# Rev_A.net
KiCad netlist of a schematic drawn in EAGLE
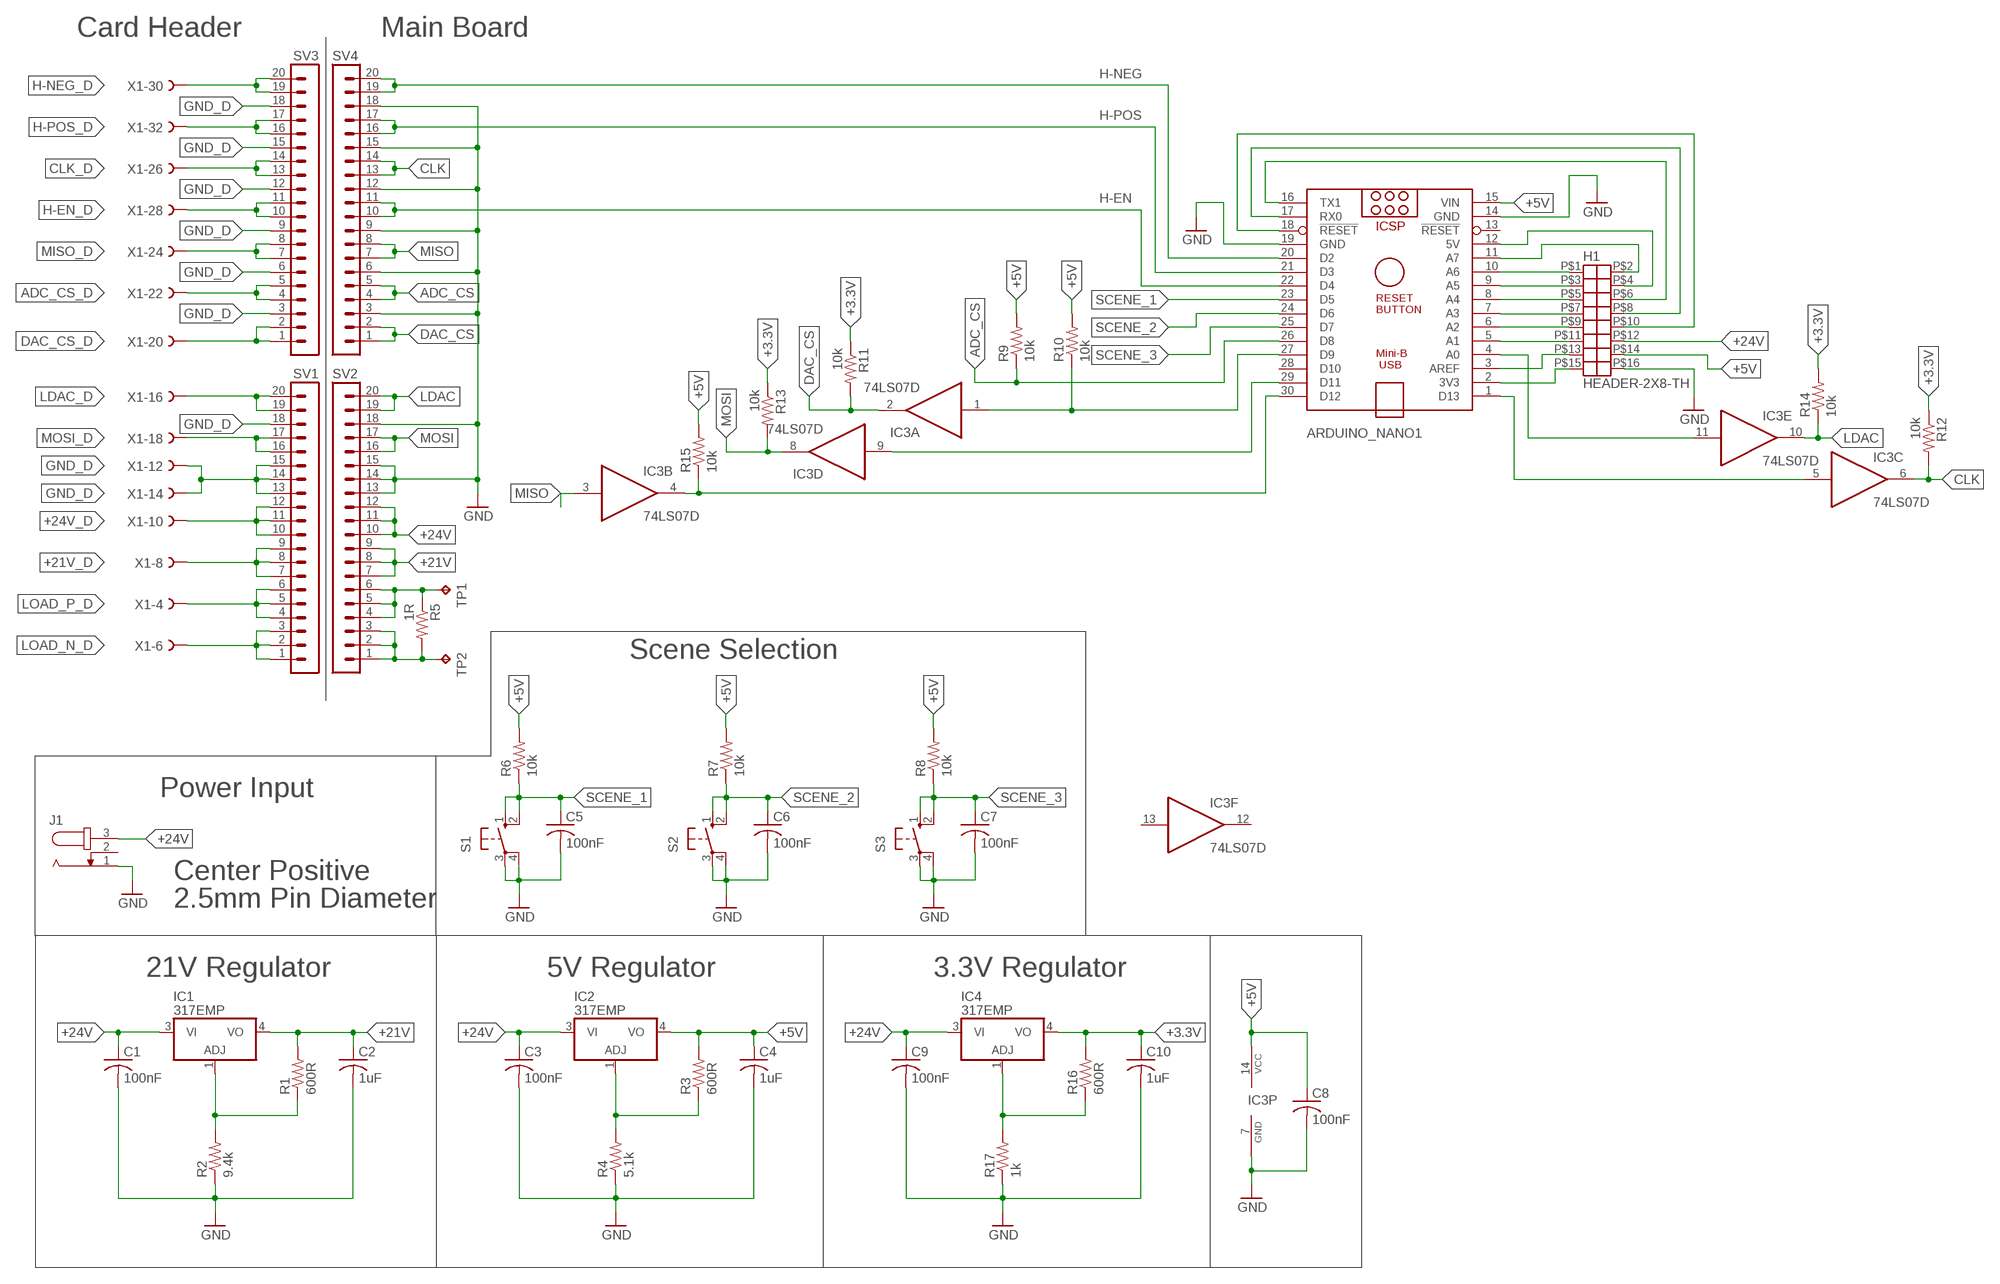
[diagram p0: schematic, sheet 1]

(export (version "E")
  (design (tool "Eeschema 10.0.6"))
  (components
    (comp (ref "ARDUINO_NANO1")
      (value "ARDUINO_NANO")
      (footprint "eagle-import:ARDUINO_NANO")
      (libsource (lib "eagle-import") (part "ARDUINO_NANO"))
    )
    (comp (ref "C1")
      (value "100nF")
      (footprint "eagle-import:C0603")
      (libsource (lib "eagle-import") (part "C-USC0603"))
    )
    (comp (ref "C2")
      (value "1uF")
      (footprint "eagle-import:C1206")
      (libsource (lib "eagle-import") (part "C-USC1206"))
    )
    (comp (ref "C3")
      (value "100nF")
      (footprint "eagle-import:C0603")
      (libsource (lib "eagle-import") (part "C-USC0603"))
    )
    (comp (ref "C4")
      (value "1uF")
      (footprint "eagle-import:C1206")
      (libsource (lib "eagle-import") (part "C-USC1206"))
    )
    (comp (ref "C5")
      (value "100nF")
      (footprint "eagle-import:C0603")
      (libsource (lib "eagle-import") (part "C-USC0603"))
    )
    (comp (ref "C6")
      (value "100nF")
      (footprint "eagle-import:C0603")
      (libsource (lib "eagle-import") (part "C-USC0603"))
    )
    (comp (ref "C7")
      (value "100nF")
      (footprint "eagle-import:C0603")
      (libsource (lib "eagle-import") (part "C-USC0603"))
    )
    (comp (ref "C8")
      (value "100nF")
      (footprint "eagle-import:C0603")
      (libsource (lib "eagle-import") (part "C-USC0603"))
    )
    (comp (ref "C9")
      (value "100nF")
      (footprint "eagle-import:C0603")
      (libsource (lib "eagle-import") (part "C-USC0603"))
    )
    (comp (ref "C10")
      (value "1uF")
      (footprint "eagle-import:C1206")
      (libsource (lib "eagle-import") (part "C-USC1206"))
    )
    (comp (ref "H1")
      (value "HEADER-2X8-TH")
      (footprint "eagle-import:HEADER-2X8-TH")
      (libsource (lib "eagle-import") (part "HEADER-2X8-TH"))
    )
    (comp (ref "IC1")
      (value "317EMP")
      (footprint "eagle-import:SOT223")
      (libsource (lib "eagle-import") (part "317EMP"))
    )
    (comp (ref "IC2")
      (value "317EMP")
      (footprint "eagle-import:SOT223")
      (libsource (lib "eagle-import") (part "317EMP"))
    )
    (comp (ref "IC3")
      (value "74LS07D")
      (footprint "eagle-import:SO14")
      (libsource (lib "eagle-import") (part "7407DLS"))
    )
    (comp (ref "IC4")
      (value "317EMP")
      (footprint "eagle-import:SOT223")
      (libsource (lib "eagle-import") (part "317EMP"))
    )
    (comp (ref "J1")
      (value "JACK-PLUG1")
      (footprint "eagle-import:SPC4078")
      (libsource (lib "eagle-import") (part "JACK-PLUG1"))
    )
    (comp (ref "R1")
      (value "600R")
      (footprint "eagle-import:R0603")
      (libsource (lib "eagle-import") (part "R-US_R0603"))
    )
    (comp (ref "R2")
      (value "9.4k")
      (footprint "eagle-import:R0603")
      (libsource (lib "eagle-import") (part "R-US_R0603"))
    )
    (comp (ref "R3")
      (value "600R")
      (footprint "eagle-import:R0603")
      (libsource (lib "eagle-import") (part "R-US_R0603"))
    )
    (comp (ref "R4")
      (value "5.1k")
      (footprint "eagle-import:R0603")
      (libsource (lib "eagle-import") (part "R-US_R0603"))
    )
    (comp (ref "R5")
      (value "1R")
      (footprint "eagle-import:R1206")
      (libsource (lib "eagle-import") (part "R-US_R1206"))
    )
    (comp (ref "R6")
      (value "10k")
      (footprint "eagle-import:R0603")
      (libsource (lib "eagle-import") (part "R-US_R0603"))
    )
    (comp (ref "R7")
      (value "10k")
      (footprint "eagle-import:R0603")
      (libsource (lib "eagle-import") (part "R-US_R0603"))
    )
    (comp (ref "R8")
      (value "10k")
      (footprint "eagle-import:R0603")
      (libsource (lib "eagle-import") (part "R-US_R0603"))
    )
    (comp (ref "R9")
      (value "10k")
      (footprint "eagle-import:R0603")
      (libsource (lib "eagle-import") (part "R-US_R0603"))
    )
    (comp (ref "R10")
      (value "10k")
      (footprint "eagle-import:R0603")
      (libsource (lib "eagle-import") (part "R-US_R0603"))
    )
    (comp (ref "R11")
      (value "10k")
      (footprint "eagle-import:R0603")
      (libsource (lib "eagle-import") (part "R-US_R0603"))
    )
    (comp (ref "R12")
      (value "10k")
      (footprint "eagle-import:R0603")
      (libsource (lib "eagle-import") (part "R-US_R0603"))
    )
    (comp (ref "R13")
      (value "10k")
      (footprint "eagle-import:R0603")
      (libsource (lib "eagle-import") (part "R-US_R0603"))
    )
    (comp (ref "R14")
      (value "10k")
      (footprint "eagle-import:R0603")
      (libsource (lib "eagle-import") (part "R-US_R0603"))
    )
    (comp (ref "R15")
      (value "10k")
      (footprint "eagle-import:R0603")
      (libsource (lib "eagle-import") (part "R-US_R0603"))
    )
    (comp (ref "R16")
      (value "600R")
      (footprint "eagle-import:R0603")
      (libsource (lib "eagle-import") (part "R-US_R0603"))
    )
    (comp (ref "R17")
      (value "1k")
      (footprint "eagle-import:R0603")
      (libsource (lib "eagle-import") (part "R-US_R0603"))
    )
    (comp (ref "S1")
      (value "10-XX")
      (footprint "eagle-import:B3F-10XX")
      (fields (field (name "MPN") "B3F-1000"))
      (libsource (lib "eagle-import") (part "10-XX"))
    )
    (comp (ref "S2")
      (value "10-XX")
      (footprint "eagle-import:B3F-10XX")
      (fields (field (name "MPN") "B3F-1000"))
      (libsource (lib "eagle-import") (part "10-XX"))
    )
    (comp (ref "S3")
      (value "10-XX")
      (footprint "eagle-import:B3F-10XX")
      (fields (field (name "MPN") "B3F-1000"))
      (libsource (lib "eagle-import") (part "10-XX"))
    )
    (comp (ref "SV1")
      (value "MA20-1")
      (footprint "eagle-import:MA20-1")
      (libsource (lib "eagle-import") (part "MA20-1"))
    )
    (comp (ref "SV2")
      (value "MA20-1W")
      (footprint "eagle-import:MA20-1W")
      (libsource (lib "eagle-import") (part "MA20-1W"))
    )
    (comp (ref "SV3")
      (value "MA20-1")
      (footprint "eagle-import:MA20-1")
      (libsource (lib "eagle-import") (part "MA20-1"))
    )
    (comp (ref "SV4")
      (value "MA20-1W")
      (footprint "eagle-import:MA20-1W")
      (libsource (lib "eagle-import") (part "MA20-1W"))
    )
    (comp (ref "TP1")
      (value "TPB2,54")
      (footprint "eagle-import:B2,54")
      (libsource (lib "eagle-import") (part "TPB2,54"))
    )
    (comp (ref "TP2")
      (value "TPB2,54")
      (footprint "eagle-import:B2,54")
      (libsource (lib "eagle-import") (part "TPB2,54"))
    )
    (comp (ref "X1")
      (value "FH15")
      (footprint "eagle-import:FH15")
      (libsource (lib "eagle-import") (part "FH15"))
    )
  )
  (nets
    (net (code "1") (name "+3.3V") (class "Default")
      (node (ref "C10") (pin "1") (pinfunction "1_1") (pintype "passive"))
      (node (ref "IC4") (pin "4") (pinfunction "VO_4") (pintype "passive"))
      (node (ref "R11") (pin "1") (pinfunction "1_1") (pintype "passive"))
      (node (ref "R12") (pin "1") (pinfunction "1_1") (pintype "passive"))
      (node (ref "R13") (pin "1") (pinfunction "1_1") (pintype "passive"))
      (node (ref "R14") (pin "2") (pinfunction "2_2") (pintype "passive"))
      (node (ref "R16") (pin "2") (pinfunction "2_2") (pintype "passive"))
    )
    (net (code "2") (name "+5V") (class "Default")
      (node (ref "ARDUINO_NANO1") (pin "15") (pinfunction "VIN_15") (pintype "power_in"))
      (node (ref "C4") (pin "1") (pinfunction "1_1") (pintype "passive"))
      (node (ref "C8") (pin "1") (pinfunction "1_1") (pintype "passive"))
      (node (ref "H1") (pin "P$14") (pinfunction "P$14_P$14") (pintype "bidirectional"))
      (node (ref "IC2") (pin "4") (pinfunction "VO_4") (pintype "passive"))
      (node (ref "IC3") (pin "14") (pinfunction "VCC_14") (pintype "power_in"))
      (node (ref "R10") (pin "2") (pinfunction "2_2") (pintype "passive"))
      (node (ref "R15") (pin "2") (pinfunction "2_2") (pintype "passive"))
      (node (ref "R3") (pin "2") (pinfunction "2_2") (pintype "passive"))
      (node (ref "R6") (pin "2") (pinfunction "2_2") (pintype "passive"))
      (node (ref "R7") (pin "2") (pinfunction "2_2") (pintype "passive"))
      (node (ref "R8") (pin "2") (pinfunction "2_2") (pintype "passive"))
      (node (ref "R9") (pin "2") (pinfunction "2_2") (pintype "passive"))
    )
    (net (code "3") (name "+21V") (class "Default")
      (node (ref "C2") (pin "1") (pinfunction "1_1") (pintype "passive"))
      (node (ref "IC1") (pin "4") (pinfunction "VO_4") (pintype "passive"))
      (node (ref "R1") (pin "2") (pinfunction "2_2") (pintype "passive"))
      (node (ref "SV2") (pin "7") (pinfunction "7_7") (pintype "passive"))
      (node (ref "SV2") (pin "8") (pinfunction "8_8") (pintype "passive"))
      (node (ref "SV2") (pin "9") (pinfunction "9_9") (pintype "passive"))
    )
    (net (code "4") (name "+21V_D") (class "Default")
      (node (ref "SV1") (pin "7") (pinfunction "7_7") (pintype "passive"))
      (node (ref "SV1") (pin "8") (pinfunction "8_8") (pintype "passive"))
      (node (ref "SV1") (pin "9") (pinfunction "9_9") (pintype "passive"))
      (node (ref "X1") (pin "8") (pinfunction "B_8") (pintype "passive"))
    )
    (net (code "5") (name "+24V") (class "Default")
      (node (ref "C1") (pin "1") (pinfunction "1_1") (pintype "passive"))
      (node (ref "C3") (pin "1") (pinfunction "1_1") (pintype "passive"))
      (node (ref "C9") (pin "1") (pinfunction "1_1") (pintype "passive"))
      (node (ref "H1") (pin "P$12") (pinfunction "P$12_P$12") (pintype "bidirectional"))
      (node (ref "IC1") (pin "3") (pinfunction "VI_3") (pintype "input"))
      (node (ref "IC2") (pin "3") (pinfunction "VI_3") (pintype "input"))
      (node (ref "IC4") (pin "3") (pinfunction "VI_3") (pintype "input"))
      (node (ref "J1") (pin "3") (pinfunction "3_3") (pintype "passive"))
      (node (ref "SV2") (pin "10") (pinfunction "10_10") (pintype "passive"))
      (node (ref "SV2") (pin "11") (pinfunction "11_11") (pintype "passive"))
      (node (ref "SV2") (pin "12") (pinfunction "12_12") (pintype "passive"))
    )
    (net (code "6") (name "+24V_D") (class "Default")
      (node (ref "SV1") (pin "10") (pinfunction "10_10") (pintype "passive"))
      (node (ref "SV1") (pin "11") (pinfunction "11_11") (pintype "passive"))
      (node (ref "SV1") (pin "12") (pinfunction "12_12") (pintype "passive"))
      (node (ref "X1") (pin "10") (pinfunction "B_10") (pintype "passive"))
    )
    (net (code "7") (name "ADC_CS") (class "Default")
      (node (ref "ARDUINO_NANO1") (pin "26") (pinfunction "D8_26") (pintype "bidirectional"))
      (node (ref "R9") (pin "1") (pinfunction "1_1") (pintype "passive"))
      (node (ref "SV4") (pin "4") (pinfunction "4_4") (pintype "passive"))
      (node (ref "SV4") (pin "5") (pinfunction "5_5") (pintype "passive"))
    )
    (net (code "8") (name "ADC_CS_D") (class "Default")
      (node (ref "SV3") (pin "4") (pinfunction "4_4") (pintype "passive"))
      (node (ref "SV3") (pin "5") (pinfunction "5_5") (pintype "passive"))
      (node (ref "X1") (pin "22") (pinfunction "B_22") (pintype "passive"))
    )
    (net (code "9") (name "CLK") (class "Default")
      (node (ref "IC3") (pin "6") (pinfunction "O_6") (pintype "open_collector"))
      (node (ref "R12") (pin "2") (pinfunction "2_2") (pintype "passive"))
      (node (ref "SV4") (pin "13") (pinfunction "13_13") (pintype "passive"))
      (node (ref "SV4") (pin "14") (pinfunction "14_14") (pintype "passive"))
    )
    (net (code "10") (name "CLK_D") (class "Default")
      (node (ref "SV3") (pin "13") (pinfunction "13_13") (pintype "passive"))
      (node (ref "SV3") (pin "14") (pinfunction "14_14") (pintype "passive"))
      (node (ref "X1") (pin "26") (pinfunction "B_26") (pintype "passive"))
    )
    (net (code "11") (name "DAC_CS") (class "Default")
      (node (ref "IC3") (pin "2") (pinfunction "O_2") (pintype "open_collector"))
      (node (ref "R11") (pin "2") (pinfunction "2_2") (pintype "passive"))
      (node (ref "SV4") (pin "1") (pinfunction "1_1") (pintype "passive"))
      (node (ref "SV4") (pin "2") (pinfunction "2_2") (pintype "passive"))
    )
    (net (code "12") (name "DAC_CS_D") (class "Default")
      (node (ref "SV3") (pin "1") (pinfunction "1_1") (pintype "passive"))
      (node (ref "SV3") (pin "2") (pinfunction "2_2") (pintype "passive"))
      (node (ref "X1") (pin "20") (pinfunction "B_20") (pintype "passive"))
    )
    (net (code "13") (name "GND") (class "Default")
      (node (ref "ARDUINO_NANO1") (pin "14") (pinfunction "GND_14") (pintype "power_in"))
      (node (ref "ARDUINO_NANO1") (pin "19") (pinfunction "GND_19") (pintype "power_in"))
      (node (ref "C1") (pin "2") (pinfunction "2_2") (pintype "passive"))
      (node (ref "C10") (pin "2") (pinfunction "2_2") (pintype "passive"))
      (node (ref "C2") (pin "2") (pinfunction "2_2") (pintype "passive"))
      (node (ref "C3") (pin "2") (pinfunction "2_2") (pintype "passive"))
      (node (ref "C4") (pin "2") (pinfunction "2_2") (pintype "passive"))
      (node (ref "C5") (pin "2") (pinfunction "2_2") (pintype "passive"))
      (node (ref "C6") (pin "2") (pinfunction "2_2") (pintype "passive"))
      (node (ref "C7") (pin "2") (pinfunction "2_2") (pintype "passive"))
      (node (ref "C8") (pin "2") (pinfunction "2_2") (pintype "passive"))
      (node (ref "C9") (pin "2") (pinfunction "2_2") (pintype "passive"))
      (node (ref "H1") (pin "P$16") (pinfunction "P$16_P$16") (pintype "bidirectional"))
      (node (ref "IC3") (pin "7") (pinfunction "GND_7") (pintype "power_in"))
      (node (ref "J1") (pin "1") (pinfunction "1_1") (pintype "passive"))
      (node (ref "R17") (pin "1") (pinfunction "1_1") (pintype "passive"))
      (node (ref "R2") (pin "1") (pinfunction "1_1") (pintype "passive"))
      (node (ref "R4") (pin "1") (pinfunction "1_1") (pintype "passive"))
      (node (ref "S1") (pin "3") (pinfunction "P_3") (pintype "passive"))
      (node (ref "S1") (pin "4") (pinfunction "P1_4") (pintype "passive"))
      (node (ref "S2") (pin "3") (pinfunction "P_3") (pintype "passive"))
      (node (ref "S2") (pin "4") (pinfunction "P1_4") (pintype "passive"))
      (node (ref "S3") (pin "3") (pinfunction "P_3") (pintype "passive"))
      (node (ref "S3") (pin "4") (pinfunction "P1_4") (pintype "passive"))
      (node (ref "SV2") (pin "13") (pinfunction "13_13") (pintype "passive"))
      (node (ref "SV2") (pin "14") (pinfunction "14_14") (pintype "passive"))
      (node (ref "SV2") (pin "15") (pinfunction "15_15") (pintype "passive"))
      (node (ref "SV2") (pin "18") (pinfunction "18_18") (pintype "passive"))
      (node (ref "SV4") (pin "12") (pinfunction "12_12") (pintype "passive"))
      (node (ref "SV4") (pin "15") (pinfunction "15_15") (pintype "passive"))
      (node (ref "SV4") (pin "18") (pinfunction "18_18") (pintype "passive"))
      (node (ref "SV4") (pin "3") (pinfunction "3_3") (pintype "passive"))
      (node (ref "SV4") (pin "6") (pinfunction "6_6") (pintype "passive"))
      (node (ref "SV4") (pin "9") (pinfunction "9_9") (pintype "passive"))
    )
    (net (code "14") (name "GND_D") (class "Default")
      (node (ref "SV1") (pin "13") (pinfunction "13_13") (pintype "passive"))
      (node (ref "SV1") (pin "14") (pinfunction "14_14") (pintype "passive"))
      (node (ref "SV1") (pin "15") (pinfunction "15_15") (pintype "passive"))
      (node (ref "SV1") (pin "18") (pinfunction "18_18") (pintype "passive"))
      (node (ref "SV3") (pin "12") (pinfunction "12_12") (pintype "passive"))
      (node (ref "SV3") (pin "15") (pinfunction "15_15") (pintype "passive"))
      (node (ref "SV3") (pin "18") (pinfunction "18_18") (pintype "passive"))
      (node (ref "SV3") (pin "3") (pinfunction "3_3") (pintype "passive"))
      (node (ref "SV3") (pin "6") (pinfunction "6_6") (pintype "passive"))
      (node (ref "SV3") (pin "9") (pinfunction "9_9") (pintype "passive"))
      (node (ref "X1") (pin "12") (pinfunction "B_12") (pintype "passive"))
      (node (ref "X1") (pin "14") (pinfunction "B_14") (pintype "passive"))
    )
    (net (code "15") (name "H-EN_D") (class "Default")
      (node (ref "SV3") (pin "10") (pinfunction "10_10") (pintype "passive"))
      (node (ref "SV3") (pin "11") (pinfunction "11_11") (pintype "passive"))
      (node (ref "X1") (pin "28") (pinfunction "B_28") (pintype "passive"))
    )
    (net (code "16") (name "H-NEG_D") (class "Default")
      (node (ref "SV3") (pin "19") (pinfunction "19_19") (pintype "passive"))
      (node (ref "SV3") (pin "20") (pinfunction "20_20") (pintype "passive"))
      (node (ref "X1") (pin "30") (pinfunction "B_30") (pintype "passive"))
    )
    (net (code "17") (name "H-POS_D") (class "Default")
      (node (ref "SV3") (pin "16") (pinfunction "16_16") (pintype "passive"))
      (node (ref "SV3") (pin "17") (pinfunction "17_17") (pintype "passive"))
      (node (ref "X1") (pin "32") (pinfunction "B_32") (pintype "passive"))
    )
    (net (code "18") (name "LDAC") (class "Default")
      (node (ref "IC3") (pin "10") (pinfunction "O_10") (pintype "open_collector"))
      (node (ref "R14") (pin "1") (pinfunction "1_1") (pintype "passive"))
      (node (ref "SV2") (pin "19") (pinfunction "19_19") (pintype "passive"))
      (node (ref "SV2") (pin "20") (pinfunction "20_20") (pintype "passive"))
    )
    (net (code "19") (name "LDAC_D") (class "Default")
      (node (ref "SV1") (pin "19") (pinfunction "19_19") (pintype "passive"))
      (node (ref "SV1") (pin "20") (pinfunction "20_20") (pintype "passive"))
      (node (ref "X1") (pin "16") (pinfunction "B_16") (pintype "passive"))
    )
    (net (code "20") (name "LOAD_N_D") (class "Default")
      (node (ref "SV1") (pin "1") (pinfunction "1_1") (pintype "passive"))
      (node (ref "SV1") (pin "2") (pinfunction "2_2") (pintype "passive"))
      (node (ref "SV1") (pin "3") (pinfunction "3_3") (pintype "passive"))
      (node (ref "X1") (pin "6") (pinfunction "B_6") (pintype "passive"))
    )
    (net (code "21") (name "LOAD_P_D") (class "Default")
      (node (ref "SV1") (pin "4") (pinfunction "4_4") (pintype "passive"))
      (node (ref "SV1") (pin "5") (pinfunction "5_5") (pintype "passive"))
      (node (ref "SV1") (pin "6") (pinfunction "6_6") (pintype "passive"))
      (node (ref "X1") (pin "4") (pinfunction "B_4") (pintype "passive"))
    )
    (net (code "22") (name "MISO") (class "Default")
      (node (ref "IC3") (pin "3") (pinfunction "I_3") (pintype "input"))
      (node (ref "SV4") (pin "7") (pinfunction "7_7") (pintype "passive"))
      (node (ref "SV4") (pin "8") (pinfunction "8_8") (pintype "passive"))
    )
    (net (code "23") (name "MISO_D") (class "Default")
      (node (ref "SV3") (pin "7") (pinfunction "7_7") (pintype "passive"))
      (node (ref "SV3") (pin "8") (pinfunction "8_8") (pintype "passive"))
      (node (ref "X1") (pin "24") (pinfunction "B_24") (pintype "passive"))
    )
    (net (code "24") (name "MOSI") (class "Default")
      (node (ref "IC3") (pin "8") (pinfunction "O_8") (pintype "open_collector"))
      (node (ref "R13") (pin "2") (pinfunction "2_2") (pintype "passive"))
      (node (ref "SV2") (pin "16") (pinfunction "16_16") (pintype "passive"))
      (node (ref "SV2") (pin "17") (pinfunction "17_17") (pintype "passive"))
    )
    (net (code "25") (name "MOSI_D") (class "Default")
      (node (ref "SV1") (pin "16") (pinfunction "16_16") (pintype "passive"))
      (node (ref "SV1") (pin "17") (pinfunction "17_17") (pintype "passive"))
      (node (ref "X1") (pin "18") (pinfunction "B_18") (pintype "passive"))
    )
    (net (code "26") (name "Net-(ARDUINO_NANO1-3V3)") (class "Default")
      (node (ref "ARDUINO_NANO1") (pin "2") (pinfunction "3V3_2") (pintype "output"))
      (node (ref "H1") (pin "P$15") (pinfunction "P$15_P$15") (pintype "bidirectional"))
    )
    (net (code "27") (name "Net-(ARDUINO_NANO1-5V)") (class "Default")
      (node (ref "ARDUINO_NANO1") (pin "12") (pinfunction "5V_12") (pintype "power_in"))
      (node (ref "H1") (pin "P$4") (pinfunction "P$4_P$4") (pintype "bidirectional"))
    )
    (net (code "28") (name "Net-(ARDUINO_NANO1-A0)") (class "Default")
      (node (ref "ARDUINO_NANO1") (pin "4") (pinfunction "A0_4") (pintype "bidirectional"))
      (node (ref "IC3") (pin "11") (pinfunction "I_11") (pintype "input"))
    )
    (net (code "29") (name "Net-(ARDUINO_NANO1-A1)") (class "Default")
      (node (ref "ARDUINO_NANO1") (pin "5") (pinfunction "A1_5") (pintype "bidirectional"))
      (node (ref "H1") (pin "P$11") (pinfunction "P$11_P$11") (pintype "bidirectional"))
    )
    (net (code "30") (name "Net-(ARDUINO_NANO1-A2)") (class "Default")
      (node (ref "ARDUINO_NANO1") (pin "6") (pinfunction "A2_6") (pintype "bidirectional"))
      (node (ref "H1") (pin "P$9") (pinfunction "P$9_P$9") (pintype "bidirectional"))
    )
    (net (code "31") (name "Net-(ARDUINO_NANO1-A3)") (class "Default")
      (node (ref "ARDUINO_NANO1") (pin "7") (pinfunction "A3_7") (pintype "bidirectional"))
      (node (ref "H1") (pin "P$7") (pinfunction "P$7_P$7") (pintype "bidirectional"))
    )
    (net (code "32") (name "Net-(ARDUINO_NANO1-A4)") (class "Default")
      (node (ref "ARDUINO_NANO1") (pin "8") (pinfunction "A4_8") (pintype "bidirectional"))
      (node (ref "H1") (pin "P$5") (pinfunction "P$5_P$5") (pintype "bidirectional"))
    )
    (net (code "33") (name "Net-(ARDUINO_NANO1-A5)") (class "Default")
      (node (ref "ARDUINO_NANO1") (pin "9") (pinfunction "A5_9") (pintype "bidirectional"))
      (node (ref "H1") (pin "P$3") (pinfunction "P$3_P$3") (pintype "bidirectional"))
    )
    (net (code "34") (name "Net-(ARDUINO_NANO1-A6)") (class "Default")
      (node (ref "ARDUINO_NANO1") (pin "10") (pinfunction "A6_10") (pintype "bidirectional"))
      (node (ref "H1") (pin "P$1") (pinfunction "P$1_P$1") (pintype "bidirectional"))
    )
    (net (code "35") (name "Net-(ARDUINO_NANO1-A7)") (class "Default")
      (node (ref "ARDUINO_NANO1") (pin "11") (pinfunction "A7_11") (pintype "bidirectional"))
      (node (ref "H1") (pin "P$2") (pinfunction "P$2_P$2") (pintype "bidirectional"))
    )
    (net (code "36") (name "Net-(ARDUINO_NANO1-AREF)") (class "Default")
      (node (ref "ARDUINO_NANO1") (pin "3") (pinfunction "AREF_3") (pintype "input"))
      (node (ref "H1") (pin "P$13") (pinfunction "P$13_P$13") (pintype "bidirectional"))
    )
    (net (code "37") (name "Net-(ARDUINO_NANO1-D2)") (class "Default")
      (node (ref "ARDUINO_NANO1") (pin "20") (pinfunction "D2_20") (pintype "bidirectional"))
      (node (ref "SV4") (pin "19") (pinfunction "19_19") (pintype "passive"))
      (node (ref "SV4") (pin "20") (pinfunction "20_20") (pintype "passive"))
    )
    (net (code "38") (name "Net-(ARDUINO_NANO1-D3)") (class "Default")
      (node (ref "ARDUINO_NANO1") (pin "21") (pinfunction "D3_21") (pintype "bidirectional"))
      (node (ref "SV4") (pin "16") (pinfunction "16_16") (pintype "passive"))
      (node (ref "SV4") (pin "17") (pinfunction "17_17") (pintype "passive"))
    )
    (net (code "39") (name "Net-(ARDUINO_NANO1-D4)") (class "Default")
      (node (ref "ARDUINO_NANO1") (pin "22") (pinfunction "D4_22") (pintype "bidirectional"))
      (node (ref "SV4") (pin "10") (pinfunction "10_10") (pintype "passive"))
      (node (ref "SV4") (pin "11") (pinfunction "11_11") (pintype "passive"))
    )
    (net (code "40") (name "Net-(ARDUINO_NANO1-D9)") (class "Default")
      (node (ref "ARDUINO_NANO1") (pin "27") (pinfunction "D9_27") (pintype "bidirectional"))
      (node (ref "IC3") (pin "1") (pinfunction "I_1") (pintype "input"))
      (node (ref "R10") (pin "1") (pinfunction "1_1") (pintype "passive"))
    )
    (net (code "41") (name "Net-(ARDUINO_NANO1-D11)") (class "Default")
      (node (ref "ARDUINO_NANO1") (pin "29") (pinfunction "D11_29") (pintype "bidirectional"))
      (node (ref "IC3") (pin "9") (pinfunction "I_9") (pintype "input"))
    )
    (net (code "42") (name "Net-(ARDUINO_NANO1-D12)") (class "Default")
      (node (ref "ARDUINO_NANO1") (pin "30") (pinfunction "D12_30") (pintype "bidirectional"))
      (node (ref "IC3") (pin "4") (pinfunction "O_4") (pintype "open_collector"))
      (node (ref "R15") (pin "1") (pinfunction "1_1") (pintype "passive"))
    )
    (net (code "43") (name "Net-(ARDUINO_NANO1-D13)") (class "Default")
      (node (ref "ARDUINO_NANO1") (pin "1") (pinfunction "D13_1") (pintype "bidirectional"))
      (node (ref "IC3") (pin "5") (pinfunction "I_5") (pintype "input"))
    )
    (net (code "44") (name "Net-(ARDUINO_NANO1-RX0)") (class "Default")
      (node (ref "ARDUINO_NANO1") (pin "17") (pinfunction "RX0_17") (pintype "bidirectional"))
      (node (ref "H1") (pin "P$8") (pinfunction "P$8_P$8") (pintype "bidirectional"))
    )
    (net (code "45") (name "Net-(ARDUINO_NANO1-TX1)") (class "Default")
      (node (ref "ARDUINO_NANO1") (pin "16") (pinfunction "TX1_16") (pintype "bidirectional"))
      (node (ref "H1") (pin "P$6") (pinfunction "P$6_P$6") (pintype "bidirectional"))
    )
    (net (code "46") (name "Net-(ARDUINO_NANO1-~{RESET}-Pad18)") (class "Default")
      (node (ref "ARDUINO_NANO1") (pin "18") (pinfunction "~{RESET}_18") (pintype "input"))
      (node (ref "H1") (pin "P$10") (pinfunction "P$10_P$10") (pintype "bidirectional"))
    )
    (net (code "47") (name "Net-(IC1-ADJ)") (class "Default")
      (node (ref "IC1") (pin "1") (pinfunction "ADJ_1") (pintype "input"))
      (node (ref "R1") (pin "1") (pinfunction "1_1") (pintype "passive"))
      (node (ref "R2") (pin "2") (pinfunction "2_2") (pintype "passive"))
    )
    (net (code "48") (name "Net-(IC2-ADJ)") (class "Default")
      (node (ref "IC2") (pin "1") (pinfunction "ADJ_1") (pintype "input"))
      (node (ref "R3") (pin "1") (pinfunction "1_1") (pintype "passive"))
      (node (ref "R4") (pin "2") (pinfunction "2_2") (pintype "passive"))
    )
    (net (code "49") (name "Net-(IC4-ADJ)") (class "Default")
      (node (ref "IC4") (pin "1") (pinfunction "ADJ_1") (pintype "input"))
      (node (ref "R16") (pin "1") (pinfunction "1_1") (pintype "passive"))
      (node (ref "R17") (pin "2") (pinfunction "2_2") (pintype "passive"))
    )
    (net (code "50") (name "Net-(R5-Pad1)") (class "Default")
      (node (ref "R5") (pin "1") (pinfunction "1_1") (pintype "passive"))
      (node (ref "SV2") (pin "4") (pinfunction "4_4") (pintype "passive"))
      (node (ref "SV2") (pin "5") (pinfunction "5_5") (pintype "passive"))
      (node (ref "SV2") (pin "6") (pinfunction "6_6") (pintype "passive"))
      (node (ref "TP1") (pin "TP") (pinfunction "TP_TP") (pintype "input"))
    )
    (net (code "51") (name "Net-(R5-Pad2)") (class "Default")
      (node (ref "R5") (pin "2") (pinfunction "2_2") (pintype "passive"))
      (node (ref "SV2") (pin "1") (pinfunction "1_1") (pintype "passive"))
      (node (ref "SV2") (pin "2") (pinfunction "2_2") (pintype "passive"))
      (node (ref "SV2") (pin "3") (pinfunction "3_3") (pintype "passive"))
      (node (ref "TP2") (pin "TP") (pinfunction "TP_TP") (pintype "input"))
    )
    (net (code "52") (name "SCENE_1") (class "Default")
      (node (ref "ARDUINO_NANO1") (pin "23") (pinfunction "D5_23") (pintype "bidirectional"))
      (node (ref "C5") (pin "1") (pinfunction "1_1") (pintype "passive"))
      (node (ref "R6") (pin "1") (pinfunction "1_1") (pintype "passive"))
      (node (ref "S1") (pin "1") (pinfunction "S_1") (pintype "passive"))
      (node (ref "S1") (pin "2") (pinfunction "S1_2") (pintype "passive"))
    )
    (net (code "53") (name "SCENE_2") (class "Default")
      (node (ref "ARDUINO_NANO1") (pin "24") (pinfunction "D6_24") (pintype "bidirectional"))
      (node (ref "C6") (pin "1") (pinfunction "1_1") (pintype "passive"))
      (node (ref "R7") (pin "1") (pinfunction "1_1") (pintype "passive"))
      (node (ref "S2") (pin "1") (pinfunction "S_1") (pintype "passive"))
      (node (ref "S2") (pin "2") (pinfunction "S1_2") (pintype "passive"))
    )
    (net (code "54") (name "SCENE_3") (class "Default")
      (node (ref "ARDUINO_NANO1") (pin "25") (pinfunction "D7_25") (pintype "bidirectional"))
      (node (ref "C7") (pin "1") (pinfunction "1_1") (pintype "passive"))
      (node (ref "R8") (pin "1") (pinfunction "1_1") (pintype "passive"))
      (node (ref "S3") (pin "1") (pinfunction "S_1") (pintype "passive"))
      (node (ref "S3") (pin "2") (pinfunction "S1_2") (pintype "passive"))
    )
    (net (code "55") (name "unconnected-(ARDUINO_NANO1-D10-Pad28)") (class "Default")
      (node (ref "ARDUINO_NANO1") (pin "28") (pinfunction "D10_28") (pintype "bidirectional"))
    )
    (net (code "56") (name "unconnected-(ARDUINO_NANO1-~{RESET}-Pad13)") (class "Default")
      (node (ref "ARDUINO_NANO1") (pin "13") (pinfunction "~{RESET}_13") (pintype "input"))
    )
    (net (code "57") (name "unconnected-(IC3F-I-Pad13)") (class "Default")
      (node (ref "IC3") (pin "13") (pinfunction "I_13") (pintype "input"))
    )
    (net (code "58") (name "unconnected-(IC3F-O-Pad12)") (class "Default")
      (node (ref "IC3") (pin "12") (pinfunction "O_12") (pintype "open_collector"))
    )
    (net (code "59") (name "unconnected-(J1-Pad2)") (class "Default")
      (node (ref "J1") (pin "2") (pinfunction "2_2") (pintype "passive"))
    )
  )
)
